# Supplies.net
KiCad netlist of a schematic drawn in Altium Designer
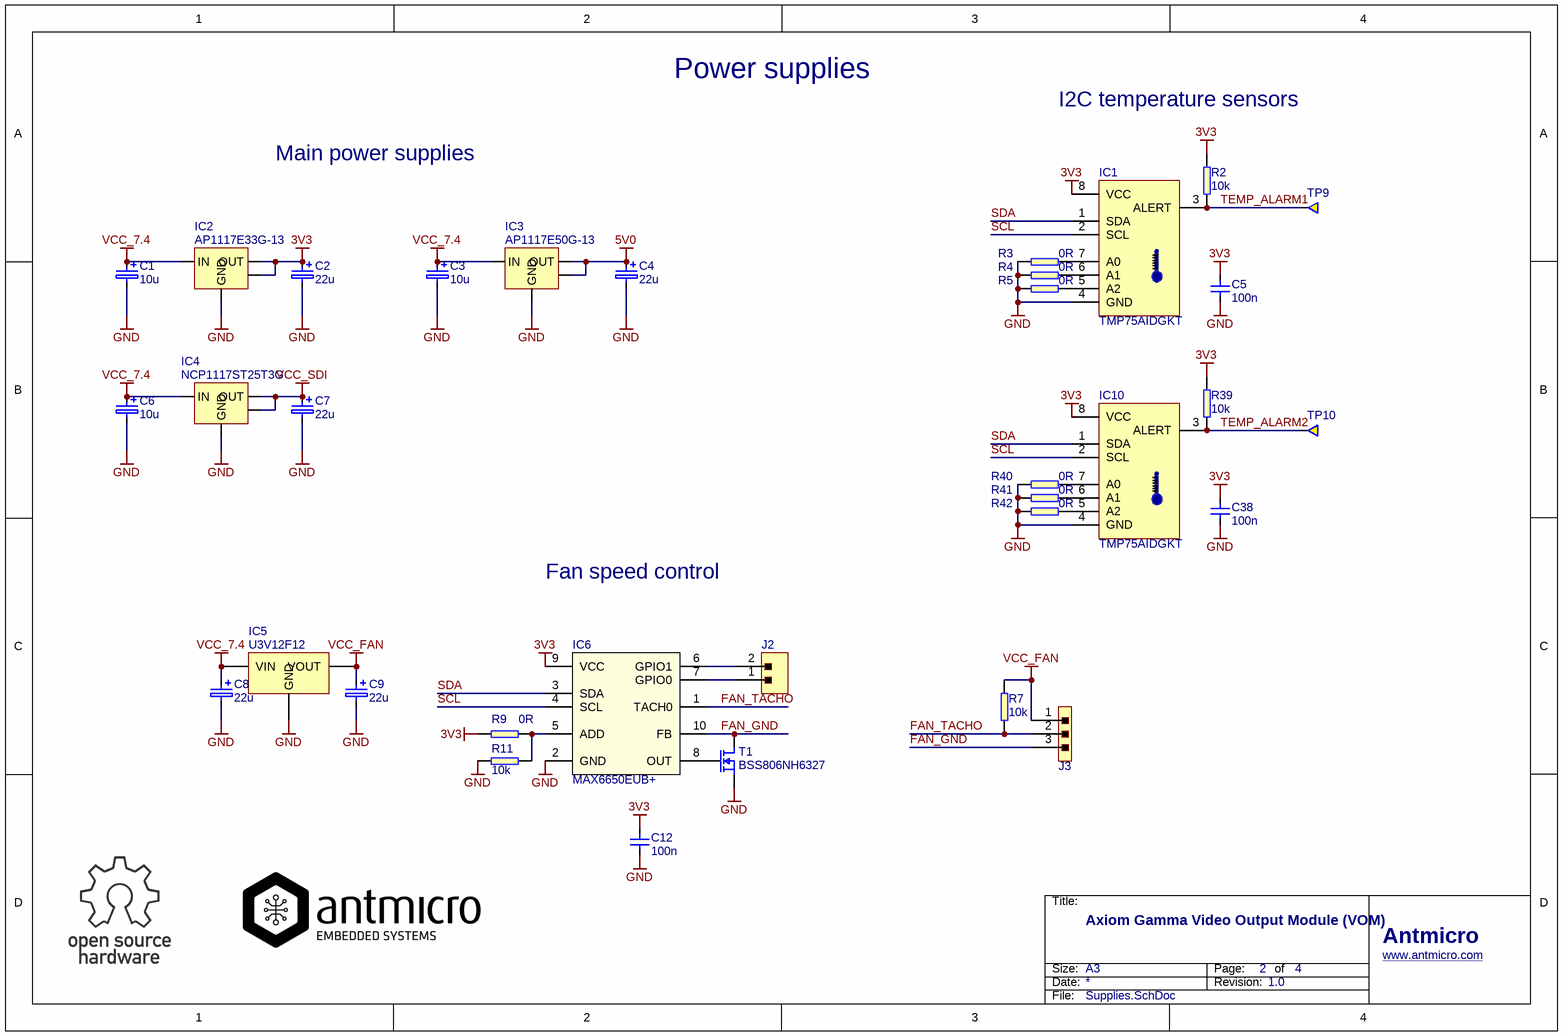
[diagram p0: Supplies.SchDoc]

(export (version "E")
  (design (tool "Eeschema 10.0.6"))
  (components
    (comp (ref "C1")
      (value "10u")
      (footprint "KEMET_C")
      (description "Tantalum SMT Capacitor 10uF Case KEMET_C")
      (fields (field (name "PART NUMBER") "C_10u_KEMET_C") (field (name "MANUFACTURER") "KEMET"))
      (libsource (lib "VOM") (part "CPol_10u"))
    )
    (comp (ref "C2")
      (value "22u")
      (footprint "KEMET_C")
      (description "Tantalum SMT Capacitor 22uF Case KEMET_C")
      (fields (field (name "PART NUMBER") "C_22u_KEMET_C") (field (name "MANUFACTURER") "KEMET"))
      (libsource (lib "VOM") (part "CPol_22u"))
    )
    (comp (ref "C3")
      (value "10u")
      (footprint "KEMET_C")
      (description "Tantalum SMT Capacitor 10uF Case KEMET_C")
      (fields (field (name "PART NUMBER") "C_10u_KEMET_C") (field (name "MANUFACTURER") "KEMET"))
      (libsource (lib "VOM") (part "CPol_10u"))
    )
    (comp (ref "C4")
      (value "22u")
      (footprint "KEMET_C")
      (description "Tantalum SMT Capacitor 22uF Case KEMET_C")
      (fields (field (name "PART NUMBER") "C_22u_KEMET_C") (field (name "MANUFACTURER") "KEMET"))
      (libsource (lib "VOM") (part "CPol_22u"))
    )
    (comp (ref "C5")
      (value "100n")
      (footprint "0402")
      (description "MLCC SMT Capacitor 0402")
      (fields (field (name "PART NUMBER") "C_100n_0402") (field (name "MANUFACTURER") "MULTICOMP"))
      (libsource (lib "VOM") (part "C_100n_0402"))
    )
    (comp (ref "C6")
      (value "10u")
      (footprint "KEMET_C")
      (description "Tantalum SMT Capacitor 10uF Case KEMET_C")
      (fields (field (name "PART NUMBER") "C_10u_KEMET_C") (field (name "MANUFACTURER") "KEMET"))
      (libsource (lib "VOM") (part "CPol_10u"))
    )
    (comp (ref "C7")
      (value "22u")
      (footprint "KEMET_C")
      (description "Tantalum SMT Capacitor 22uF Case KEMET_C")
      (fields (field (name "PART NUMBER") "C_22u_KEMET_C") (field (name "MANUFACTURER") "KEMET"))
      (libsource (lib "VOM") (part "CPol_22u"))
    )
    (comp (ref "C8")
      (value "22u")
      (footprint "KEMET_C")
      (description "Tantalum SMT Capacitor 22uF Case KEMET_C")
      (fields (field (name "PART NUMBER") "C_22u_KEMET_C") (field (name "MANUFACTURER") "KEMET"))
      (libsource (lib "VOM") (part "CPol_22u"))
    )
    (comp (ref "C9")
      (value "22u")
      (footprint "KEMET_C")
      (description "Tantalum SMT Capacitor 22uF Case KEMET_C")
      (fields (field (name "PART NUMBER") "C_22u_KEMET_C") (field (name "MANUFACTURER") "KEMET"))
      (libsource (lib "VOM") (part "CPol_22u"))
    )
    (comp (ref "C12")
      (value "100n")
      (footprint "0402")
      (description "MLCC SMT Capacitor 0402")
      (fields (field (name "PART NUMBER") "C_100n_0402") (field (name "MANUFACTURER") "MULTICOMP"))
      (libsource (lib "VOM") (part "C_100n_0402"))
    )
    (comp (ref "C38")
      (value "100n")
      (footprint "0402")
      (description "MLCC SMT Capacitor 0402")
      (fields (field (name "PART NUMBER") "C_100n_0402") (field (name "MANUFACTURER") "MULTICOMP"))
      (libsource (lib "VOM") (part "C_100n_0402"))
    )
    (comp (ref "IC1")
      (value "TMP75AIDGKT")
      (footprint "MSOP-8")
      (description "Temperature Sensor With I2C and SMBus Interface in Industry Standard LM75")
      (fields (field (name "MANUFACTURER") "TEXAS INSTRUMENTS"))
      (libsource (lib "VOM") (part "TMP75"))
    )
    (comp (ref "IC2")
      (value "AP1117E33G-13")
      (footprint "SOT223")
      (description "IC, LDO, REG, 3.3V, SOT223")
      (fields (field (name "MANUFACTURER") "DIODES INC."))
      (libsource (lib "VOM") (part "AP1117E33G-13"))
    )
    (comp (ref "IC3")
      (value "AP1117E50G-13")
      (footprint "SOT223")
      (description "IC, LDO, REG, 5.0V, SOT223")
      (fields (field (name "MANUFACTURER") "DIODES INC."))
      (libsource (lib "VOM") (part "AP1117E50G-13"))
    )
    (comp (ref "IC4")
      (value "NCP1117ST25T3G")
      (footprint "SOT223")
      (description "IC, LDO, REG, 2.5V, SOT223")
      (fields (field (name "MANUFACTURER") "ON Semiconductor"))
      (libsource (lib "VOM") (part "NCP1117ST25T3G"))
    )
    (comp (ref "IC5")
      (value "U3V12F12")
      (footprint "U3V12Fxx")
      (description "Pololu 9V Step-Up Voltage Regulator")
      (fields (field (name "MANUFACTURER") "TME"))
      (libsource (lib "VOM") (part "U3V12F12"))
    )
    (comp (ref "IC6")
      (value "MAX6650EUB+")
      (footprint "uMAX10")
      (description "Fan-Speed Regulator and Monitor with SMBus/I2C-Compatible Interface")
      (fields (field (name "MANUFACTURER") "MAXIM INTEGRATED"))
      (libsource (lib "VOM") (part "MAX6650"))
    )
    (comp (ref "IC10")
      (value "TMP75AIDGKT")
      (footprint "MSOP-8")
      (description "Temperature Sensor With I2C and SMBus Interface in Industry Standard LM75")
      (fields (field (name "MANUFACTURER") "TEXAS INSTRUMENTS"))
      (libsource (lib "VOM") (part "TMP75"))
    )
    (comp (ref "J2")
      (value "MH_1X02_2.54")
      (footprint "MH_1X02_2.54")
      (description "Male header, 1 x 02 pins, pitch 2.54 mm")
      (fields (field (name "MANUFACTURER") "MULTICOMP"))
      (libsource (lib "VOM") (part "1X02"))
    )
    (comp (ref "J3")
      (value "Molex 022232031")
      (footprint "molex_2223-2031")
      (fields (field (name "PART NUMBER") "molex_2223-2031") (field (name "MANUFACTURER") "Molex"))
      (libsource (lib "VOM") (part "1X03"))
    )
    (comp (ref "R2")
      (value "10k")
      (footprint "0402")
      (description "SMT Resistor 0402")
      (fields (field (name "PART NUMBER") "R_10k_0402") (field (name "MANUFACTURER") "MULTICOMP"))
      (libsource (lib "VOM") (part "R_10k_0402"))
    )
    (comp (ref "R3")
      (value "0R")
      (footprint "0603")
      (description "SMT Resistor 0R 0603")
      (fields (field (name "PART NUMBER") "R_0R_0603") (field (name "MANUFACTURER") "BOURNS"))
      (libsource (lib "VOM") (part "R_0R_0603"))
    )
    (comp (ref "R4")
      (value "0R")
      (footprint "0603")
      (description "SMT Resistor 0R 0603")
      (fields (field (name "PART NUMBER") "R_0R_0603") (field (name "MANUFACTURER") "BOURNS"))
      (libsource (lib "VOM") (part "R_0R_0603"))
    )
    (comp (ref "R5")
      (value "0R")
      (footprint "0603")
      (description "SMT Resistor 0R 0603")
      (fields (field (name "PART NUMBER") "R_0R_0603") (field (name "MANUFACTURER") "BOURNS"))
      (libsource (lib "VOM") (part "R_0R_0603"))
    )
    (comp (ref "R7")
      (value "10k")
      (footprint "0402")
      (description "SMT Resistor 0402")
      (fields (field (name "PART NUMBER") "R_10k_0402") (field (name "MANUFACTURER") "MULTICOMP"))
      (libsource (lib "VOM") (part "R_10k_0402"))
    )
    (comp (ref "R9")
      (value "0R")
      (footprint "0603")
      (description "SMT Resistor 0R 0603")
      (fields (field (name "PART NUMBER") "R_0R_0603") (field (name "MANUFACTURER") "BOURNS"))
      (libsource (lib "") (part "R_0R_0603_1"))
    )
    (comp (ref "R11")
      (value "10k")
      (footprint "0603")
      (description "SMT Resistor 0R 0603")
      (fields (field (name "PART NUMBER") "R_10k_0603") (field (name "MANUFACTURER") "BOURNS"))
      (libsource (lib "VOM") (part "R_10k_0603"))
    )
    (comp (ref "R39")
      (value "10k")
      (footprint "0402")
      (description "SMT Resistor 0402")
      (fields (field (name "PART NUMBER") "R_10k_0402") (field (name "MANUFACTURER") "MULTICOMP"))
      (libsource (lib "VOM") (part "R_10k_0402"))
    )
    (comp (ref "R40")
      (value "0R")
      (footprint "0603")
      (description "SMT Resistor 0R 0603")
      (fields (field (name "PART NUMBER") "R_0R_0603") (field (name "MANUFACTURER") "BOURNS"))
      (libsource (lib "VOM") (part "R_0R_0603"))
    )
    (comp (ref "R41")
      (value "0R")
      (footprint "0603")
      (description "SMT Resistor 0R 0603")
      (fields (field (name "PART NUMBER") "R_0R_0603") (field (name "MANUFACTURER") "BOURNS"))
      (libsource (lib "VOM") (part "R_0R_0603"))
    )
    (comp (ref "R42")
      (value "0R")
      (footprint "0603")
      (description "SMT Resistor 0R 0603")
      (fields (field (name "PART NUMBER") "R_0R_0603") (field (name "MANUFACTURER") "BOURNS"))
      (libsource (lib "VOM") (part "R_0R_0603"))
    )
    (comp (ref "T1")
      (value "BSS806NH6327")
      (footprint "SOT-23")
      (description "MOSFET, BRT, N CH, 2.3 A, 20 V, 0.041 ohm, 2.5 V, 550 mV")
      (fields (field (name "MANUFACTURER") "INFINEON"))
      (libsource (lib "VOM") (part "BSS806NH6327"))
    )
    (comp (ref "TP9")
      (value "Testpad")
      (footprint "Testpad")
      (description "Testpad 2mm diameter")
      (fields (field (name "MANUFACTURER") "PCB ONLY"))
      (libsource (lib "VOM") (part "Testpad"))
    )
    (comp (ref "TP10")
      (value "Testpad")
      (footprint "Testpad")
      (description "Testpad 2mm diameter")
      (fields (field (name "MANUFACTURER") "PCB ONLY"))
      (libsource (lib "VOM") (part "Testpad"))
    )
  )
  (nets
    (net (code "1") (name "/FAN_GND") (class "Default")
      (node (ref "IC6") (pin "10") (pinfunction "FB_10") (pintype "passive"))
      (node (ref "J3") (pin "3") (pinfunction "3_3") (pintype "passive"))
      (node (ref "T1") (pin "3") (pinfunction "D_3") (pintype "passive"))
    )
    (net (code "2") (name "/FAN_TACHO") (class "Default")
      (node (ref "IC6") (pin "1") (pinfunction "TACH0_1") (pintype "passive"))
      (node (ref "J3") (pin "2") (pinfunction "2_2") (pintype "passive"))
      (node (ref "R7") (pin "1") (pintype "passive"))
    )
    (net (code "3") (name "/SCL") (class "Default")
      (node (ref "IC1") (pin "2") (pinfunction "SCL_2") (pintype "passive"))
      (node (ref "IC10") (pin "2") (pinfunction "SCL_2") (pintype "passive"))
      (node (ref "IC6") (pin "4") (pinfunction "SCL_4") (pintype "passive"))
    )
    (net (code "4") (name "/SDA") (class "Default")
      (node (ref "IC1") (pin "1") (pinfunction "SDA_1") (pintype "passive"))
      (node (ref "IC10") (pin "1") (pinfunction "SDA_1") (pintype "passive"))
      (node (ref "IC6") (pin "3") (pinfunction "SDA_3") (pintype "passive"))
    )
    (net (code "5") (name "/TEMP_ALARM1") (class "Default")
      (node (ref "IC1") (pin "3") (pinfunction "ALERT_3") (pintype "passive"))
      (node (ref "R2") (pin "1") (pintype "passive"))
      (node (ref "TP9") (pin "1") (pintype "passive"))
    )
    (net (code "6") (name "/TEMP_ALARM2") (class "Default")
      (node (ref "IC10") (pin "3") (pinfunction "ALERT_3") (pintype "passive"))
      (node (ref "R39") (pin "1") (pintype "passive"))
      (node (ref "TP10") (pin "1") (pintype "passive"))
    )
    (net (code "7") (name "3V3") (class "Default")
      (node (ref "C12") (pin "1") (pinfunction "1_1") (pintype "passive"))
      (node (ref "C2") (pin "1") (pinfunction "1_1") (pintype "passive"))
      (node (ref "C38") (pin "1") (pinfunction "1_1") (pintype "passive"))
      (node (ref "C5") (pin "1") (pinfunction "1_1") (pintype "passive"))
      (node (ref "IC1") (pin "8") (pinfunction "VCC_8") (pintype "passive"))
      (node (ref "IC10") (pin "8") (pinfunction "VCC_8") (pintype "passive"))
      (node (ref "IC2") (pin "2") (pinfunction "OUT_2") (pintype "passive"))
      (node (ref "IC2") (pin "4") (pinfunction "OUT_4") (pintype "passive"))
      (node (ref "IC6") (pin "9") (pinfunction "VCC_9") (pintype "passive"))
      (node (ref "R2") (pin "2") (pintype "passive"))
      (node (ref "R39") (pin "2") (pintype "passive"))
      (node (ref "R9") (pin "1") (pintype "passive"))
    )
    (net (code "8") (name "5V0") (class "Default")
      (node (ref "C4") (pin "1") (pinfunction "1_1") (pintype "passive"))
      (node (ref "IC3") (pin "2") (pinfunction "OUT_2") (pintype "passive"))
      (node (ref "IC3") (pin "4") (pinfunction "OUT_4") (pintype "passive"))
    )
    (net (code "9") (name "GND") (class "Default")
      (node (ref "C1") (pin "2") (pinfunction "2_2") (pintype "passive"))
      (node (ref "C12") (pin "2") (pinfunction "2_2") (pintype "passive"))
      (node (ref "C2") (pin "2") (pinfunction "2_2") (pintype "passive"))
      (node (ref "C3") (pin "2") (pinfunction "2_2") (pintype "passive"))
      (node (ref "C38") (pin "2") (pinfunction "2_2") (pintype "passive"))
      (node (ref "C4") (pin "2") (pinfunction "2_2") (pintype "passive"))
      (node (ref "C5") (pin "2") (pinfunction "2_2") (pintype "passive"))
      (node (ref "C6") (pin "2") (pinfunction "2_2") (pintype "passive"))
      (node (ref "C7") (pin "2") (pinfunction "2_2") (pintype "passive"))
      (node (ref "C8") (pin "2") (pinfunction "2_2") (pintype "passive"))
      (node (ref "C9") (pin "2") (pinfunction "2_2") (pintype "passive"))
      (node (ref "IC1") (pin "4") (pinfunction "GND_4") (pintype "passive"))
      (node (ref "IC10") (pin "4") (pinfunction "GND_4") (pintype "passive"))
      (node (ref "IC2") (pin "1") (pinfunction "GND_1") (pintype "power_in"))
      (node (ref "IC3") (pin "1") (pinfunction "GND_1") (pintype "power_in"))
      (node (ref "IC4") (pin "1") (pinfunction "GND_1") (pintype "power_in"))
      (node (ref "IC5") (pin "2") (pinfunction "GND_2") (pintype "power_in"))
      (node (ref "IC6") (pin "2") (pinfunction "GND_2") (pintype "passive"))
      (node (ref "R11") (pin "1") (pintype "passive"))
      (node (ref "R3") (pin "2") (pintype "passive"))
      (node (ref "R4") (pin "2") (pintype "passive"))
      (node (ref "R40") (pin "2") (pintype "passive"))
      (node (ref "R41") (pin "2") (pintype "passive"))
      (node (ref "R42") (pin "2") (pintype "passive"))
      (node (ref "R5") (pin "2") (pintype "passive"))
      (node (ref "T1") (pin "2") (pinfunction "S_2") (pintype "passive"))
    )
    (net (code "10") (name "Net-(IC1-A0)") (class "Default")
      (node (ref "IC1") (pin "7") (pinfunction "A0_7") (pintype "passive"))
      (node (ref "R3") (pin "1") (pintype "passive"))
    )
    (net (code "11") (name "Net-(IC1-A1)") (class "Default")
      (node (ref "IC1") (pin "6") (pinfunction "A1_6") (pintype "passive"))
      (node (ref "R4") (pin "1") (pintype "passive"))
    )
    (net (code "12") (name "Net-(IC1-A2)") (class "Default")
      (node (ref "IC1") (pin "5") (pinfunction "A2_5") (pintype "passive"))
      (node (ref "R5") (pin "1") (pintype "passive"))
    )
    (net (code "13") (name "Net-(IC6-ADD)") (class "Default")
      (node (ref "IC6") (pin "5") (pinfunction "ADD_5") (pintype "passive"))
      (node (ref "R11") (pin "2") (pintype "passive"))
      (node (ref "R9") (pin "2") (pintype "passive"))
    )
    (net (code "14") (name "Net-(IC6-GPIO0)") (class "Default")
      (node (ref "IC6") (pin "7") (pinfunction "GPIO0_7") (pintype "passive"))
      (node (ref "J2") (pin "1") (pinfunction "1_1") (pintype "passive"))
    )
    (net (code "15") (name "Net-(IC6-GPIO1)") (class "Default")
      (node (ref "IC6") (pin "6") (pinfunction "GPIO1_6") (pintype "passive"))
      (node (ref "J2") (pin "2") (pinfunction "2_2") (pintype "passive"))
    )
    (net (code "16") (name "Net-(IC6-OUT)") (class "Default")
      (node (ref "IC6") (pin "8") (pinfunction "OUT_8") (pintype "passive"))
      (node (ref "T1") (pin "1") (pinfunction "G_1") (pintype "passive"))
    )
    (net (code "17") (name "Net-(IC10-A0)") (class "Default")
      (node (ref "IC10") (pin "7") (pinfunction "A0_7") (pintype "passive"))
      (node (ref "R40") (pin "1") (pintype "passive"))
    )
    (net (code "18") (name "Net-(IC10-A1)") (class "Default")
      (node (ref "IC10") (pin "6") (pinfunction "A1_6") (pintype "passive"))
      (node (ref "R41") (pin "1") (pintype "passive"))
    )
    (net (code "19") (name "Net-(IC10-A2)") (class "Default")
      (node (ref "IC10") (pin "5") (pinfunction "A2_5") (pintype "passive"))
      (node (ref "R42") (pin "1") (pintype "passive"))
    )
    (net (code "20") (name "VCC_7.4") (class "Default")
      (node (ref "C1") (pin "1") (pinfunction "1_1") (pintype "passive"))
      (node (ref "C3") (pin "1") (pinfunction "1_1") (pintype "passive"))
      (node (ref "C6") (pin "1") (pinfunction "1_1") (pintype "passive"))
      (node (ref "C8") (pin "1") (pinfunction "1_1") (pintype "passive"))
      (node (ref "IC2") (pin "3") (pinfunction "IN_3") (pintype "power_in"))
      (node (ref "IC3") (pin "3") (pinfunction "IN_3") (pintype "power_in"))
      (node (ref "IC4") (pin "3") (pinfunction "IN_3") (pintype "power_in"))
      (node (ref "IC5") (pin "1") (pinfunction "VIN_1") (pintype "power_in"))
    )
    (net (code "21") (name "VCC_FAN") (class "Default")
      (node (ref "C9") (pin "1") (pinfunction "1_1") (pintype "passive"))
      (node (ref "IC5") (pin "3") (pinfunction "VOUT_3") (pintype "power_in"))
      (node (ref "J3") (pin "1") (pinfunction "1_1") (pintype "passive"))
      (node (ref "R7") (pin "2") (pintype "passive"))
    )
    (net (code "22") (name "VCC_SDI") (class "Default")
      (node (ref "C7") (pin "1") (pinfunction "1_1") (pintype "passive"))
      (node (ref "IC4") (pin "2") (pinfunction "OUT_2") (pintype "passive"))
      (node (ref "IC4") (pin "4") (pinfunction "OUT_4") (pintype "passive"))
    )
  )
)
